# interface_dac_sma_feedback_3PS_LM317_ADC.net
KiCad netlist of a schematic drawn in EAGLE
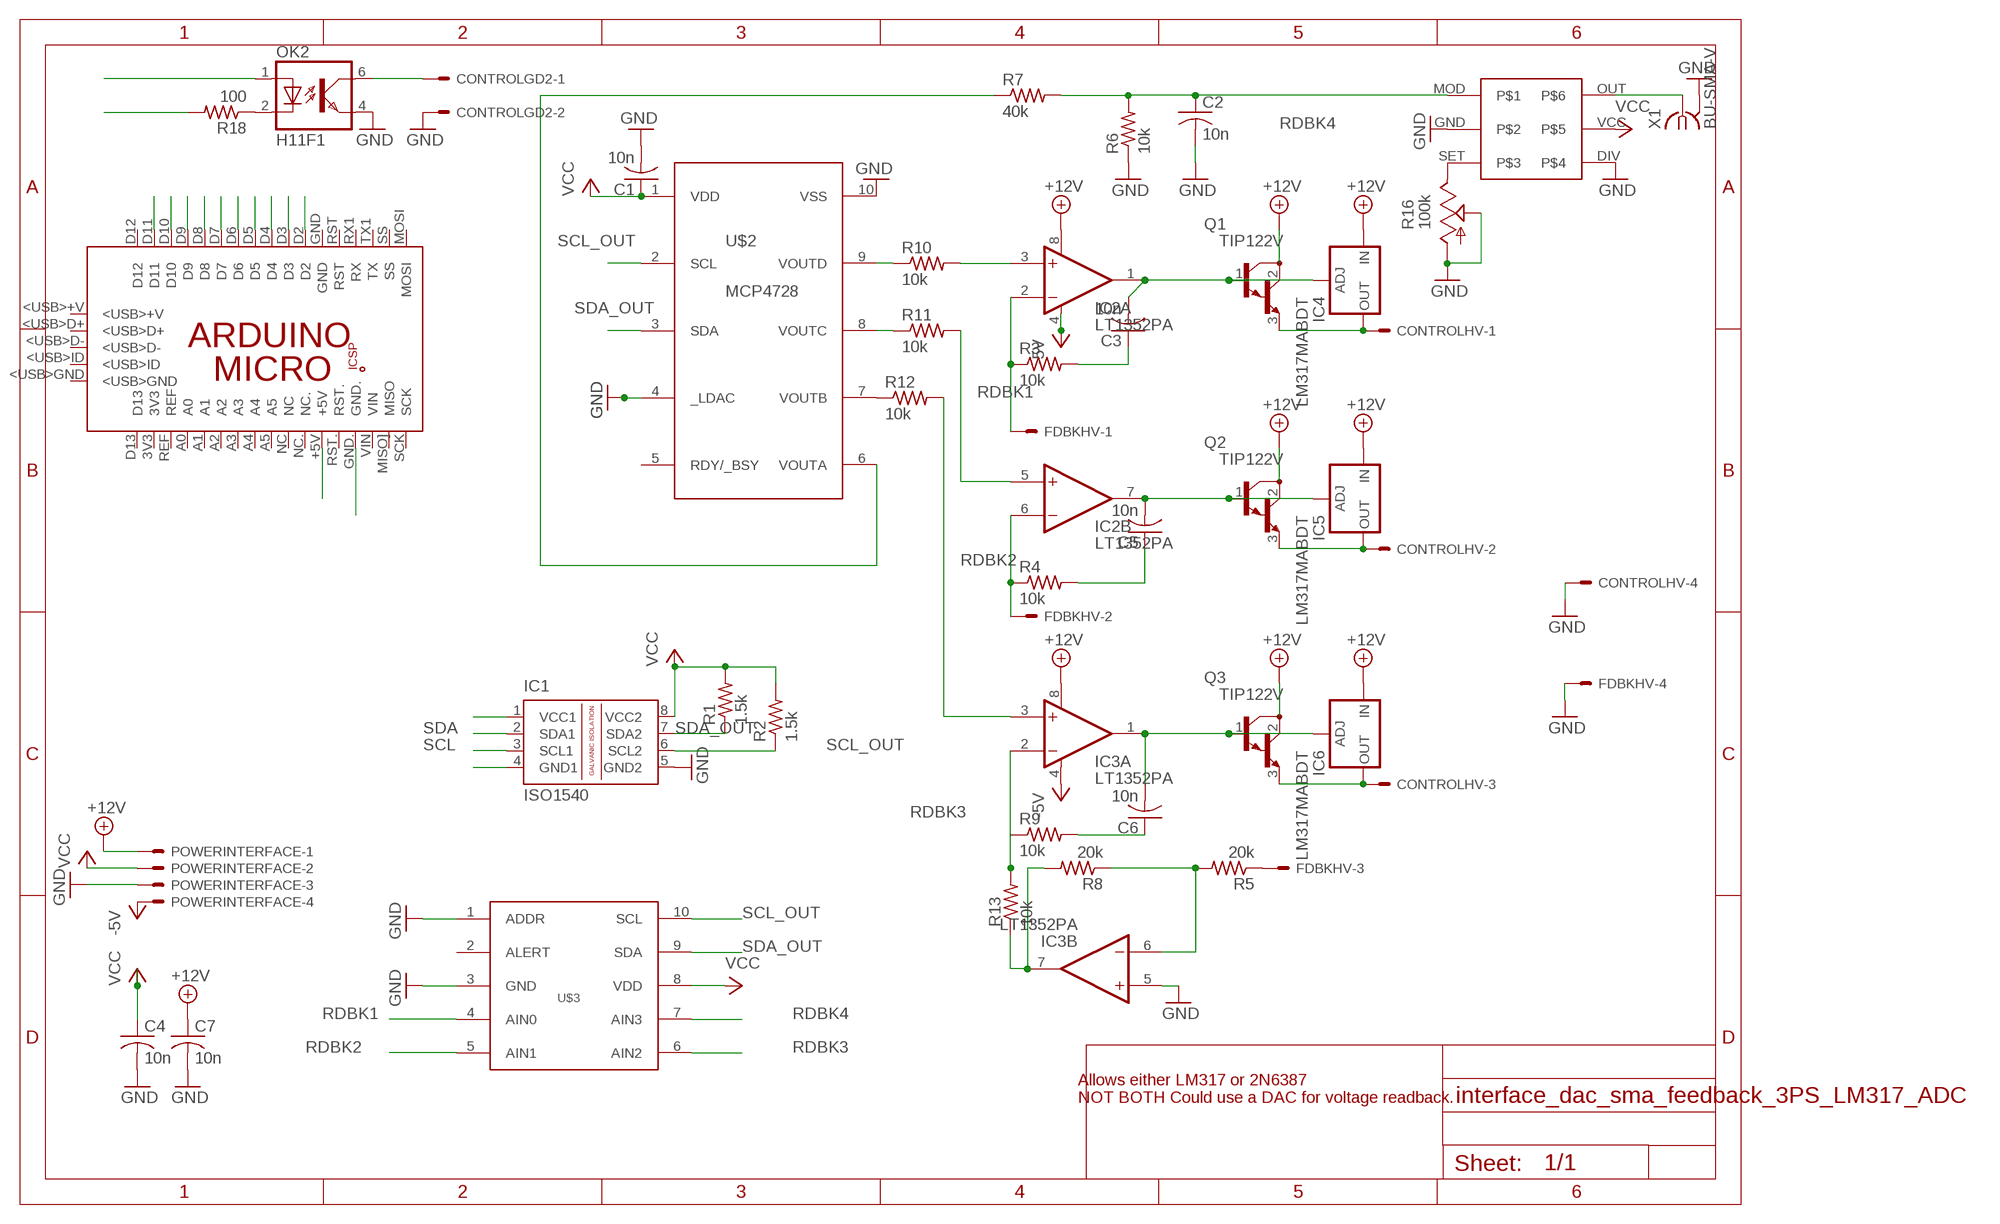
[diagram p0: schematic, sheet 1]

(export (version "E")
  (design (tool "Eeschema 10.0.6"))
  (components
    (comp (ref "C1")
      (value "10n")
      (footprint "eagle-import:C050-024X044")
      (libsource (lib "eagle-import") (part "C-US050-024X044"))
    )
    (comp (ref "C2")
      (value "10n")
      (footprint "eagle-import:C050-024X044")
      (libsource (lib "eagle-import") (part "resistor_C-US050-024X044"))
    )
    (comp (ref "C3")
      (value "10n")
      (footprint "eagle-import:C050-024X044")
      (libsource (lib "eagle-import") (part "resistor_C-US050-024X044"))
    )
    (comp (ref "C4")
      (value "10n")
      (footprint "eagle-import:C050-024X044")
      (libsource (lib "eagle-import") (part "resistor_C-US050-024X044"))
    )
    (comp (ref "C5")
      (value "10n")
      (footprint "eagle-import:C050-024X044")
      (libsource (lib "eagle-import") (part "resistor_C-US050-024X044"))
    )
    (comp (ref "C6")
      (value "10n")
      (footprint "eagle-import:C050-024X044")
      (libsource (lib "eagle-import") (part "resistor_C-US050-024X044"))
    )
    (comp (ref "C7")
      (value "10n")
      (footprint "eagle-import:C050-024X044")
      (libsource (lib "eagle-import") (part "resistor_C-US050-024X044"))
    )
    (comp (ref "CONTROLGD2")
      (value "KK-156-2")
      (footprint "eagle-import:KK-156-2")
      (libsource (lib "eagle-import") (part "KK-156-2"))
    )
    (comp (ref "CONTROLHV")
      (value "KK-156-4")
      (footprint "eagle-import:KK-156-4")
      (libsource (lib "eagle-import") (part "KK-156-4"))
    )
    (comp (ref "FDBKHV")
      (value "KK-156-4")
      (footprint "eagle-import:KK-156-4")
      (libsource (lib "eagle-import") (part "KK-156-4"))
    )
    (comp (ref "IC1")
      (value "ISO1540")
      (footprint "eagle-import:DIL08")
      (libsource (lib "eagle-import") (part "ISO1540"))
    )
    (comp (ref "IC2")
      (value "LT1352PA")
      (footprint "eagle-import:DIL08")
      (libsource (lib "eagle-import") (part "LT1352PA"))
    )
    (comp (ref "IC3")
      (value "LT1352PA")
      (footprint "eagle-import:DIL08")
      (libsource (lib "eagle-import") (part "LT1352PA"))
    )
    (comp (ref "IC4")
      (value "LM317MABDT")
      (footprint "eagle-import:DPACK")
      (libsource (lib "eagle-import") (part "v-reg_LM317?MABDT"))
    )
    (comp (ref "IC5")
      (value "LM317MABDT")
      (footprint "eagle-import:DPACK")
      (libsource (lib "eagle-import") (part "v-reg_LM317?MABDT"))
    )
    (comp (ref "IC6")
      (value "LM317MABDT")
      (footprint "eagle-import:DPACK")
      (libsource (lib "eagle-import") (part "v-reg_LM317?MABDT"))
    )
    (comp (ref "OK2")
      (value "H11F1")
      (footprint "eagle-import:DIL05")
      (libsource (lib "eagle-import") (part "H11F1"))
    )
    (comp (ref "PCB1")
      (value "ARDUINO_MICRO")
      (footprint "eagle-import:ARDUINO_MICRO")
      (libsource (lib "eagle-import") (part "ARDUINO_MICRO"))
    )
    (comp (ref "POWERINTERFACE")
      (value "KK-156-4")
      (footprint "eagle-import:KK-156-4")
      (libsource (lib "eagle-import") (part "KK-156-4"))
    )
    (comp (ref "Q1")
      (value "TIP122V")
      (footprint "eagle-import:TO220V")
      (libsource (lib "eagle-import") (part "TIP122V"))
    )
    (comp (ref "Q2")
      (value "TIP122V")
      (footprint "eagle-import:TO220V")
      (libsource (lib "eagle-import") (part "TIP122V"))
    )
    (comp (ref "Q3")
      (value "TIP122V")
      (footprint "eagle-import:TO220V")
      (libsource (lib "eagle-import") (part "TIP122V"))
    )
    (comp (ref "R1")
      (value "1.5k")
      (footprint "eagle-import:0207_12")
      (libsource (lib "eagle-import") (part "resistor_R-US_0207/12"))
    )
    (comp (ref "R2")
      (value "1.5k")
      (footprint "eagle-import:0207_12")
      (libsource (lib "eagle-import") (part "resistor_R-US_0207/12"))
    )
    (comp (ref "R3")
      (value "10k")
      (footprint "eagle-import:0207_12")
      (libsource (lib "eagle-import") (part "resistor_R-US_0207/12"))
    )
    (comp (ref "R4")
      (value "10k")
      (footprint "eagle-import:0207_12")
      (libsource (lib "eagle-import") (part "resistor_R-US_0207/12"))
    )
    (comp (ref "R5")
      (value "20k")
      (footprint "eagle-import:0207_12")
      (libsource (lib "eagle-import") (part "resistor_R-US_0207/12"))
    )
    (comp (ref "R6")
      (value "10k")
      (footprint "eagle-import:0207_12")
      (libsource (lib "eagle-import") (part "resistor_R-US_0207/12"))
    )
    (comp (ref "R7")
      (value "40k")
      (footprint "eagle-import:0207_12")
      (libsource (lib "eagle-import") (part "resistor_R-US_0207/12"))
    )
    (comp (ref "R8")
      (value "20k")
      (footprint "eagle-import:0207_12")
      (libsource (lib "eagle-import") (part "resistor_R-US_0207/12"))
    )
    (comp (ref "R9")
      (value "10k")
      (footprint "eagle-import:0207_12")
      (libsource (lib "eagle-import") (part "resistor_R-US_0207/12"))
    )
    (comp (ref "R10")
      (value "10k")
      (footprint "eagle-import:0207_12")
      (libsource (lib "eagle-import") (part "resistor_R-US_0207/12"))
    )
    (comp (ref "R11")
      (value "10k")
      (footprint "eagle-import:0207_12")
      (libsource (lib "eagle-import") (part "resistor_R-US_0207/12"))
    )
    (comp (ref "R12")
      (value "10k")
      (footprint "eagle-import:0207_12")
      (libsource (lib "eagle-import") (part "resistor_R-US_0207/12"))
    )
    (comp (ref "R13")
      (value "10k")
      (footprint "eagle-import:0207_12")
      (libsource (lib "eagle-import") (part "resistor_R-US_0207/12"))
    )
    (comp (ref "R16")
      (value "100k")
      (footprint "eagle-import:SP19L")
      (libsource (lib "eagle-import") (part "TRIM_US-B90P"))
    )
    (comp (ref "R18")
      (value "100")
      (footprint "eagle-import:0207_12")
      (libsource (lib "eagle-import") (part "R-US_0207/12"))
    )
    (comp (ref "U$1")
      (value "LTC6992")
      (footprint "eagle-import:DIL06")
      (libsource (lib "eagle-import") (part "LTC6992"))
    )
    (comp (ref "U$2")
      (value "MCP4728DIL")
      (footprint "eagle-import:DIL10")
      (libsource (lib "eagle-import") (part "MCP4728DIL"))
    )
    (comp (ref "U$3")
      (value "ADS1015DIL")
      (footprint "eagle-import:DIL10")
      (libsource (lib "eagle-import") (part "ADS1015DIL"))
    )
    (comp (ref "X1")
      (value "BU-SMA-V")
      (footprint "eagle-import:BU-SMA-V")
      (libsource (lib "eagle-import") (part "BU-SMA-V"))
    )
  )
  (nets
    (net (code "1") (name "+12V") (class "Default")
      (node (ref "C7") (pin "1") (pinfunction "1_1") (pintype "passive"))
      (node (ref "IC2") (pin "8") (pinfunction "V+_8") (pintype "power_in"))
      (node (ref "IC3") (pin "8") (pinfunction "V+_8") (pintype "power_in"))
      (node (ref "IC4") (pin "3") (pinfunction "IN_3") (pintype "input"))
      (node (ref "IC5") (pin "3") (pinfunction "IN_3") (pintype "input"))
      (node (ref "IC6") (pin "3") (pinfunction "IN_3") (pintype "input"))
      (node (ref "POWERINTERFACE") (pin "1") (pinfunction "S_1") (pintype "passive"))
      (node (ref "Q1") (pin "2") (pinfunction "C_2") (pintype "passive"))
      (node (ref "Q2") (pin "2") (pinfunction "C_2") (pintype "passive"))
      (node (ref "Q3") (pin "2") (pinfunction "C_2") (pintype "passive"))
    )
    (net (code "2") (name "-5V") (class "Default")
      (node (ref "IC2") (pin "4") (pinfunction "V-_4") (pintype "power_in"))
      (node (ref "IC3") (pin "4") (pinfunction "V-_4") (pintype "power_in"))
      (node (ref "POWERINTERFACE") (pin "4") (pinfunction "S_4") (pintype "passive"))
    )
    (net (code "3") (name "/A+5") (class "Default")
      (node (ref "IC1") (pin "1") (pinfunction "VCC1_1") (pintype "input"))
      (node (ref "PCB1") (pin "+5V") (pinfunction "+5V_+5V") (pintype "bidirectional"))
    )
    (net (code "4") (name "/AGND") (class "Default")
      (node (ref "IC1") (pin "4") (pinfunction "GND1_4") (pintype "input"))
      (node (ref "PCB1") (pin "GND.") (pinfunction "GND._GND.") (pintype "bidirectional"))
      (node (ref "R18") (pin "2") (pinfunction "2_2") (pintype "passive"))
    )
    (net (code "5") (name "/PWM9") (class "Default")
      (node (ref "OK2") (pin "1") (pinfunction "A_1") (pintype "passive"))
      (node (ref "PCB1") (pin "D9") (pinfunction "D9_D9") (pintype "bidirectional"))
    )
    (net (code "6") (name "/RDBK1") (class "Default")
      (node (ref "FDBKHV") (pin "1") (pinfunction "S_1") (pintype "passive"))
      (node (ref "IC2") (pin "2") (pinfunction "-IN_2") (pintype "input"))
      (node (ref "R3") (pin "1") (pinfunction "1_1") (pintype "passive"))
      (node (ref "U$3") (pin "4") (pinfunction "AIN0_4") (pintype "bidirectional"))
    )
    (net (code "7") (name "/RDBK2") (class "Default")
      (node (ref "FDBKHV") (pin "2") (pinfunction "S_2") (pintype "passive"))
      (node (ref "IC2") (pin "6") (pinfunction "-IN_6") (pintype "input"))
      (node (ref "R4") (pin "1") (pinfunction "1_1") (pintype "passive"))
      (node (ref "U$3") (pin "5") (pinfunction "AIN1_5") (pintype "bidirectional"))
    )
    (net (code "8") (name "/RDBK3") (class "Default")
      (node (ref "IC3") (pin "2") (pinfunction "-IN_2") (pintype "input"))
      (node (ref "R13") (pin "2") (pinfunction "2_2") (pintype "passive"))
      (node (ref "R9") (pin "1") (pinfunction "1_1") (pintype "passive"))
      (node (ref "U$3") (pin "6") (pinfunction "AIN2_6") (pintype "bidirectional"))
    )
    (net (code "9") (name "/RDBK4") (class "Default")
      (node (ref "C2") (pin "1") (pinfunction "1_1") (pintype "passive"))
      (node (ref "R6") (pin "2") (pinfunction "2_2") (pintype "passive"))
      (node (ref "R7") (pin "2") (pinfunction "2_2") (pintype "passive"))
      (node (ref "U$1") (pin "MOD") (pinfunction "P$1_MOD") (pintype "bidirectional"))
      (node (ref "U$3") (pin "7") (pinfunction "AIN3_7") (pintype "bidirectional"))
    )
    (net (code "10") (name "/SCL") (class "Default")
      (node (ref "IC1") (pin "3") (pinfunction "SCL1_3") (pintype "input"))
      (node (ref "PCB1") (pin "D3") (pinfunction "D3_D3") (pintype "bidirectional"))
    )
    (net (code "11") (name "/SCL_OUT") (class "Default")
      (node (ref "IC1") (pin "6") (pinfunction "SCL2_6") (pintype "input"))
      (node (ref "R2") (pin "1") (pinfunction "1_1") (pintype "passive"))
      (node (ref "U$2") (pin "2") (pinfunction "SCL_2") (pintype "bidirectional"))
      (node (ref "U$3") (pin "10") (pinfunction "SCL_10") (pintype "bidirectional"))
    )
    (net (code "12") (name "/SDA") (class "Default")
      (node (ref "IC1") (pin "2") (pinfunction "SDA1_2") (pintype "input"))
      (node (ref "PCB1") (pin "D2") (pinfunction "D2_D2") (pintype "bidirectional"))
    )
    (net (code "13") (name "/SDA_OUT") (class "Default")
      (node (ref "IC1") (pin "7") (pinfunction "SDA2_7") (pintype "input"))
      (node (ref "R1") (pin "1") (pinfunction "1_1") (pintype "passive"))
      (node (ref "U$2") (pin "3") (pinfunction "SDA_3") (pintype "bidirectional"))
      (node (ref "U$3") (pin "9") (pinfunction "SDA_9") (pintype "bidirectional"))
    )
    (net (code "14") (name "GND") (class "Default")
      (node (ref "C1") (pin "2") (pinfunction "2_2") (pintype "passive"))
      (node (ref "C2") (pin "2") (pinfunction "2_2") (pintype "passive"))
      (node (ref "C4") (pin "2") (pinfunction "2_2") (pintype "passive"))
      (node (ref "C7") (pin "2") (pinfunction "2_2") (pintype "passive"))
      (node (ref "CONTROLGD2") (pin "2") (pinfunction "S_2") (pintype "passive"))
      (node (ref "CONTROLHV") (pin "4") (pinfunction "S_4") (pintype "passive"))
      (node (ref "FDBKHV") (pin "4") (pinfunction "S_4") (pintype "passive"))
      (node (ref "IC1") (pin "5") (pinfunction "GND2_5") (pintype "input"))
      (node (ref "IC3") (pin "5") (pinfunction "+IN_5") (pintype "input"))
      (node (ref "OK2") (pin "4") (pinfunction "EMIT_4") (pintype "passive"))
      (node (ref "POWERINTERFACE") (pin "3") (pinfunction "S_3") (pintype "passive"))
      (node (ref "R16") (pin "A") (pinfunction "A_A") (pintype "passive"))
      (node (ref "R16") (pin "S") (pinfunction "S_S") (pintype "passive"))
      (node (ref "R6") (pin "1") (pinfunction "1_1") (pintype "passive"))
      (node (ref "U$1") (pin "DIV") (pinfunction "P$4_DIV") (pintype "bidirectional"))
      (node (ref "U$1") (pin "GND") (pinfunction "P$2_GND") (pintype "bidirectional"))
      (node (ref "U$2") (pin "10") (pinfunction "VSS_10") (pintype "bidirectional"))
      (node (ref "U$2") (pin "4") (pinfunction "_LDAC_4") (pintype "bidirectional"))
      (node (ref "U$3") (pin "1") (pinfunction "ADDR_1") (pintype "bidirectional"))
      (node (ref "U$3") (pin "3") (pinfunction "GND_3") (pintype "bidirectional"))
      (node (ref "X1") (pin "2") (pinfunction "2_2") (pintype "passive"))
      (node (ref "X1") (pin "3") (pinfunction "2_3") (pintype "passive"))
      (node (ref "X1") (pin "4") (pinfunction "2_4") (pintype "passive"))
      (node (ref "X1") (pin "5") (pinfunction "2_5") (pintype "passive"))
    )
    (net (code "15") (name "Net-(C3-Pad1)") (class "Default")
      (node (ref "C3") (pin "1") (pinfunction "1_1") (pintype "passive"))
      (node (ref "R3") (pin "2") (pinfunction "2_2") (pintype "passive"))
    )
    (net (code "16") (name "Net-(C5-Pad1)") (class "Default")
      (node (ref "C5") (pin "1") (pinfunction "1_1") (pintype "passive"))
      (node (ref "R4") (pin "2") (pinfunction "2_2") (pintype "passive"))
    )
    (net (code "17") (name "Net-(C6-Pad1)") (class "Default")
      (node (ref "C6") (pin "1") (pinfunction "1_1") (pintype "passive"))
      (node (ref "R9") (pin "2") (pinfunction "2_2") (pintype "passive"))
    )
    (net (code "18") (name "Net-(CONTROLGD2A-S)") (class "Default")
      (node (ref "CONTROLGD2") (pin "1") (pinfunction "S_1") (pintype "passive"))
      (node (ref "OK2") (pin "6") (pinfunction "COL_6") (pintype "passive"))
    )
    (net (code "19") (name "Net-(CONTROLHVA-S)") (class "Default")
      (node (ref "CONTROLHV") (pin "1") (pinfunction "S_1") (pintype "passive"))
      (node (ref "IC4") (pin "4") (pinfunction "OUT_4") (pintype "passive"))
      (node (ref "Q1") (pin "3") (pinfunction "E_3") (pintype "passive"))
    )
    (net (code "20") (name "Net-(CONTROLHVB-S)") (class "Default")
      (node (ref "CONTROLHV") (pin "2") (pinfunction "S_2") (pintype "passive"))
      (node (ref "IC5") (pin "4") (pinfunction "OUT_4") (pintype "passive"))
      (node (ref "Q2") (pin "3") (pinfunction "E_3") (pintype "passive"))
    )
    (net (code "21") (name "Net-(CONTROLHVC-S)") (class "Default")
      (node (ref "CONTROLHV") (pin "3") (pinfunction "S_3") (pintype "passive"))
      (node (ref "IC6") (pin "4") (pinfunction "OUT_4") (pintype "passive"))
      (node (ref "Q3") (pin "3") (pinfunction "E_3") (pintype "passive"))
    )
    (net (code "22") (name "Net-(FDBKHVC-S)") (class "Default")
      (node (ref "FDBKHV") (pin "3") (pinfunction "S_3") (pintype "passive"))
      (node (ref "R5") (pin "1") (pinfunction "1_1") (pintype "passive"))
    )
    (net (code "23") (name "Net-(IC2A-+IN)") (class "Default")
      (node (ref "IC2") (pin "3") (pinfunction "+IN_3") (pintype "input"))
      (node (ref "R10") (pin "2") (pinfunction "2_2") (pintype "passive"))
    )
    (net (code "24") (name "Net-(IC2A-OUT)") (class "Default")
      (node (ref "C3") (pin "2") (pinfunction "2_2") (pintype "passive"))
      (node (ref "IC2") (pin "1") (pinfunction "OUT_1") (pintype "output"))
      (node (ref "IC4") (pin "1") (pinfunction "ADJ_1") (pintype "input"))
      (node (ref "Q1") (pin "1") (pinfunction "B_1") (pintype "passive"))
    )
    (net (code "25") (name "Net-(IC2B-+IN)") (class "Default")
      (node (ref "IC2") (pin "5") (pinfunction "+IN_5") (pintype "input"))
      (node (ref "R11") (pin "2") (pinfunction "2_2") (pintype "passive"))
    )
    (net (code "26") (name "Net-(IC2B-OUT)") (class "Default")
      (node (ref "C5") (pin "2") (pinfunction "2_2") (pintype "passive"))
      (node (ref "IC2") (pin "7") (pinfunction "OUT_7") (pintype "output"))
      (node (ref "IC5") (pin "1") (pinfunction "ADJ_1") (pintype "input"))
      (node (ref "Q2") (pin "1") (pinfunction "B_1") (pintype "passive"))
    )
    (net (code "27") (name "Net-(IC3A-+IN)") (class "Default")
      (node (ref "IC3") (pin "3") (pinfunction "+IN_3") (pintype "input"))
      (node (ref "R12") (pin "2") (pinfunction "2_2") (pintype "passive"))
    )
    (net (code "28") (name "Net-(IC3A-OUT)") (class "Default")
      (node (ref "C6") (pin "2") (pinfunction "2_2") (pintype "passive"))
      (node (ref "IC3") (pin "1") (pinfunction "OUT_1") (pintype "output"))
      (node (ref "IC6") (pin "1") (pinfunction "ADJ_1") (pintype "input"))
      (node (ref "Q3") (pin "1") (pinfunction "B_1") (pintype "passive"))
    )
    (net (code "29") (name "Net-(IC3B--IN)") (class "Default")
      (node (ref "IC3") (pin "6") (pinfunction "-IN_6") (pintype "input"))
      (node (ref "R5") (pin "2") (pinfunction "2_2") (pintype "passive"))
      (node (ref "R8") (pin "1") (pinfunction "1_1") (pintype "passive"))
    )
    (net (code "30") (name "Net-(IC3B-OUT)") (class "Default")
      (node (ref "IC3") (pin "7") (pinfunction "OUT_7") (pintype "output"))
      (node (ref "R13") (pin "1") (pinfunction "1_1") (pintype "passive"))
      (node (ref "R8") (pin "2") (pinfunction "2_2") (pintype "passive"))
    )
    (net (code "31") (name "Net-(OK2-C)") (class "Default")
      (node (ref "OK2") (pin "2") (pinfunction "C_2") (pintype "passive"))
      (node (ref "R18") (pin "1") (pinfunction "1_1") (pintype "passive"))
    )
    (net (code "32") (name "Net-(U$1-P$3)") (class "Default")
      (node (ref "R16") (pin "E") (pinfunction "E_E") (pintype "passive"))
      (node (ref "U$1") (pin "SET") (pinfunction "P$3_SET") (pintype "bidirectional"))
    )
    (net (code "33") (name "Net-(U$1-P$6)") (class "Default")
      (node (ref "U$1") (pin "OUT") (pinfunction "P$6_OUT") (pintype "bidirectional"))
      (node (ref "X1") (pin "1") (pinfunction "1_1") (pintype "passive"))
    )
    (net (code "34") (name "Net-(U$2-VOUTA)") (class "Default")
      (node (ref "R7") (pin "1") (pinfunction "1_1") (pintype "passive"))
      (node (ref "U$2") (pin "6") (pinfunction "VOUTA_6") (pintype "bidirectional"))
    )
    (net (code "35") (name "Net-(U$2-VOUTB)") (class "Default")
      (node (ref "R12") (pin "1") (pinfunction "1_1") (pintype "passive"))
      (node (ref "U$2") (pin "7") (pinfunction "VOUTB_7") (pintype "bidirectional"))
    )
    (net (code "36") (name "Net-(U$2-VOUTC)") (class "Default")
      (node (ref "R11") (pin "1") (pinfunction "1_1") (pintype "passive"))
      (node (ref "U$2") (pin "8") (pinfunction "VOUTC_8") (pintype "bidirectional"))
    )
    (net (code "37") (name "Net-(U$2-VOUTD)") (class "Default")
      (node (ref "R10") (pin "1") (pinfunction "1_1") (pintype "passive"))
      (node (ref "U$2") (pin "9") (pinfunction "VOUTD_9") (pintype "bidirectional"))
    )
    (net (code "38") (name "VCC") (class "Default")
      (node (ref "C1") (pin "1") (pinfunction "1_1") (pintype "passive"))
      (node (ref "C4") (pin "1") (pinfunction "1_1") (pintype "passive"))
      (node (ref "IC1") (pin "8") (pinfunction "VCC2_8") (pintype "input"))
      (node (ref "POWERINTERFACE") (pin "2") (pinfunction "S_2") (pintype "passive"))
      (node (ref "R1") (pin "2") (pinfunction "2_2") (pintype "passive"))
      (node (ref "R2") (pin "2") (pinfunction "2_2") (pintype "passive"))
      (node (ref "U$1") (pin "VCC") (pinfunction "P$5_VCC") (pintype "bidirectional"))
      (node (ref "U$2") (pin "1") (pinfunction "VDD_1") (pintype "bidirectional"))
      (node (ref "U$3") (pin "8") (pinfunction "VDD_8") (pintype "bidirectional"))
    )
    (net (code "39") (name "unconnected-(PCB1-MISO-PadMISO])") (class "Default")
      (node (ref "PCB1") (pin "MISO]") (pinfunction "MISO_MISO]") (pintype "bidirectional"))
    )
    (net (code "40") (name "unconnected-(PCB1-Pad3V3)") (class "Default")
      (node (ref "PCB1") (pin "3V3") (pinfunction "3V3_3V3") (pintype "bidirectional"))
    )
    (net (code "41") (name "unconnected-(PCB1-Pad5V)") (class "Default")
      (node (ref "PCB1") (pin "5V") (pinfunction "5V_5V") (pintype "bidirectional"))
    )
    (net (code "42") (name "unconnected-(PCB1-Pad<USB>+V)") (class "Default")
      (node (ref "PCB1") (pin "<USB>+V") (pinfunction "<USB>+V_<USB>+V") (pintype "bidirectional"))
    )
    (net (code "43") (name "unconnected-(PCB1-Pad<USB>D+)") (class "Default")
      (node (ref "PCB1") (pin "<USB>D+") (pinfunction "<USB>D+_<USB>D+") (pintype "bidirectional"))
    )
    (net (code "44") (name "unconnected-(PCB1-Pad<USB>D-)") (class "Default")
      (node (ref "PCB1") (pin "<USB>D-") (pinfunction "<USB>D-_<USB>D-") (pintype "bidirectional"))
    )
    (net (code "45") (name "unconnected-(PCB1-Pad<USB>GND)") (class "Default")
      (node (ref "PCB1") (pin "<USB>GND") (pinfunction "<USB>GND_<USB>GND") (pintype "bidirectional"))
    )
    (net (code "46") (name "unconnected-(PCB1-Pad<USB>ID)") (class "Default")
      (node (ref "PCB1") (pin "<USB>ID") (pinfunction "<USB>ID_<USB>ID") (pintype "bidirectional"))
    )
    (net (code "47") (name "unconnected-(PCB1-PadA0)") (class "Default")
      (node (ref "PCB1") (pin "A0") (pinfunction "A0_A0") (pintype "bidirectional"))
    )
    (net (code "48") (name "unconnected-(PCB1-PadA1)") (class "Default")
      (node (ref "PCB1") (pin "A1") (pinfunction "A1_A1") (pintype "bidirectional"))
    )
    (net (code "49") (name "unconnected-(PCB1-PadA2)") (class "Default")
      (node (ref "PCB1") (pin "A2") (pinfunction "A2_A2") (pintype "bidirectional"))
    )
    (net (code "50") (name "unconnected-(PCB1-PadA3)") (class "Default")
      (node (ref "PCB1") (pin "A3") (pinfunction "A3_A3") (pintype "bidirectional"))
    )
    (net (code "51") (name "unconnected-(PCB1-PadA4)") (class "Default")
      (node (ref "PCB1") (pin "A4") (pinfunction "A4_A4") (pintype "bidirectional"))
    )
    (net (code "52") (name "unconnected-(PCB1-PadA5)") (class "Default")
      (node (ref "PCB1") (pin "A5") (pinfunction "A5_A5") (pintype "bidirectional"))
    )
    (net (code "53") (name "unconnected-(PCB1-PadD4)") (class "Default")
      (node (ref "PCB1") (pin "D4") (pinfunction "D4_D4") (pintype "bidirectional"))
    )
    (net (code "54") (name "unconnected-(PCB1-PadD5)") (class "Default")
      (node (ref "PCB1") (pin "D5") (pinfunction "D5_D5") (pintype "bidirectional"))
    )
    (net (code "55") (name "unconnected-(PCB1-PadD6)") (class "Default")
      (node (ref "PCB1") (pin "D6") (pinfunction "D6_D6") (pintype "bidirectional"))
    )
    (net (code "56") (name "unconnected-(PCB1-PadD7)") (class "Default")
      (node (ref "PCB1") (pin "D7") (pinfunction "D7_D7") (pintype "bidirectional"))
    )
    (net (code "57") (name "unconnected-(PCB1-PadD8)") (class "Default")
      (node (ref "PCB1") (pin "D8") (pinfunction "D8_D8") (pintype "bidirectional"))
    )
    (net (code "58") (name "unconnected-(PCB1-PadD10)") (class "Default")
      (node (ref "PCB1") (pin "D10") (pinfunction "D10_D10") (pintype "bidirectional"))
    )
    (net (code "59") (name "unconnected-(PCB1-PadD11)") (class "Default")
      (node (ref "PCB1") (pin "D11") (pinfunction "D11_D11") (pintype "bidirectional"))
    )
    (net (code "60") (name "unconnected-(PCB1-PadD12)") (class "Default")
      (node (ref "PCB1") (pin "D12") (pinfunction "D12_D12") (pintype "bidirectional"))
    )
    (net (code "61") (name "unconnected-(PCB1-PadD13)") (class "Default")
      (node (ref "PCB1") (pin "D13") (pinfunction "D13_D13") (pintype "bidirectional"))
    )
    (net (code "62") (name "unconnected-(PCB1-PadGND)") (class "Default")
      (node (ref "PCB1") (pin "GND") (pinfunction "GND_GND") (pintype "bidirectional"))
    )
    (net (code "63") (name "unconnected-(PCB1-PadGND_)") (class "Default")
      (node (ref "PCB1") (pin "GND_") (pinfunction "GND__GND_") (pintype "bidirectional"))
    )
    (net (code "64") (name "unconnected-(PCB1-PadMISO.)") (class "Default")
      (node (ref "PCB1") (pin "MISO.") (pinfunction "MISO._MISO.") (pintype "bidirectional"))
    )
    (net (code "65") (name "unconnected-(PCB1-PadMOSI)") (class "Default")
      (node (ref "PCB1") (pin "MOSI") (pinfunction "MOSI_MOSI") (pintype "bidirectional"))
    )
    (net (code "66") (name "unconnected-(PCB1-PadMOSI.)") (class "Default")
      (node (ref "PCB1") (pin "MOSI.") (pinfunction "MOSI._MOSI.") (pintype "bidirectional"))
    )
    (net (code "67") (name "unconnected-(PCB1-PadNC)") (class "Default")
      (node (ref "PCB1") (pin "NC") (pinfunction "NC_NC") (pintype "bidirectional"))
    )
    (net (code "68") (name "unconnected-(PCB1-PadNC.)") (class "Default")
      (node (ref "PCB1") (pin "NC.") (pinfunction "NC._NC.") (pintype "bidirectional"))
    )
    (net (code "69") (name "unconnected-(PCB1-PadREF)") (class "Default")
      (node (ref "PCB1") (pin "REF") (pinfunction "REF_REF") (pintype "bidirectional"))
    )
    (net (code "70") (name "unconnected-(PCB1-PadRESET..)") (class "Default")
      (node (ref "PCB1") (pin "RESET..") (pinfunction "RESET.._RESET..") (pintype "bidirectional"))
    )
    (net (code "71") (name "unconnected-(PCB1-PadRST)") (class "Default")
      (node (ref "PCB1") (pin "RST") (pinfunction "RST_RST") (pintype "bidirectional"))
    )
    (net (code "72") (name "unconnected-(PCB1-PadRST.)") (class "Default")
      (node (ref "PCB1") (pin "RST.") (pinfunction "RST._RST.") (pintype "bidirectional"))
    )
    (net (code "73") (name "unconnected-(PCB1-PadSCK)") (class "Default")
      (node (ref "PCB1") (pin "SCK") (pinfunction "SCK_SCK") (pintype "bidirectional"))
    )
    (net (code "74") (name "unconnected-(PCB1-PadSCK.)") (class "Default")
      (node (ref "PCB1") (pin "SCK.") (pinfunction "SCK._SCK.") (pintype "bidirectional"))
    )
    (net (code "75") (name "unconnected-(PCB1-PadSS)") (class "Default")
      (node (ref "PCB1") (pin "SS") (pinfunction "SS_SS") (pintype "bidirectional"))
    )
    (net (code "76") (name "unconnected-(PCB1-PadVIN)") (class "Default")
      (node (ref "PCB1") (pin "VIN") (pinfunction "VIN_VIN") (pintype "bidirectional"))
    )
    (net (code "77") (name "unconnected-(PCB1-RX-PadRX1)") (class "Default")
      (node (ref "PCB1") (pin "RX1") (pinfunction "RX_RX1") (pintype "bidirectional"))
    )
    (net (code "78") (name "unconnected-(PCB1-TX-PadTX1)") (class "Default")
      (node (ref "PCB1") (pin "TX1") (pinfunction "TX_TX1") (pintype "bidirectional"))
    )
    (net (code "79") (name "unconnected-(U$2-RDY{slash}_BSY-Pad5)") (class "Default")
      (node (ref "U$2") (pin "5") (pinfunction "RDY/_BSY_5") (pintype "bidirectional"))
    )
    (net (code "80") (name "unconnected-(U$3-ALERT-Pad2)") (class "Default")
      (node (ref "U$3") (pin "2") (pinfunction "ALERT_2") (pintype "bidirectional"))
    )
  )
)
